# recv_board.net
KiCad netlist of a schematic drawn in Altium Designer
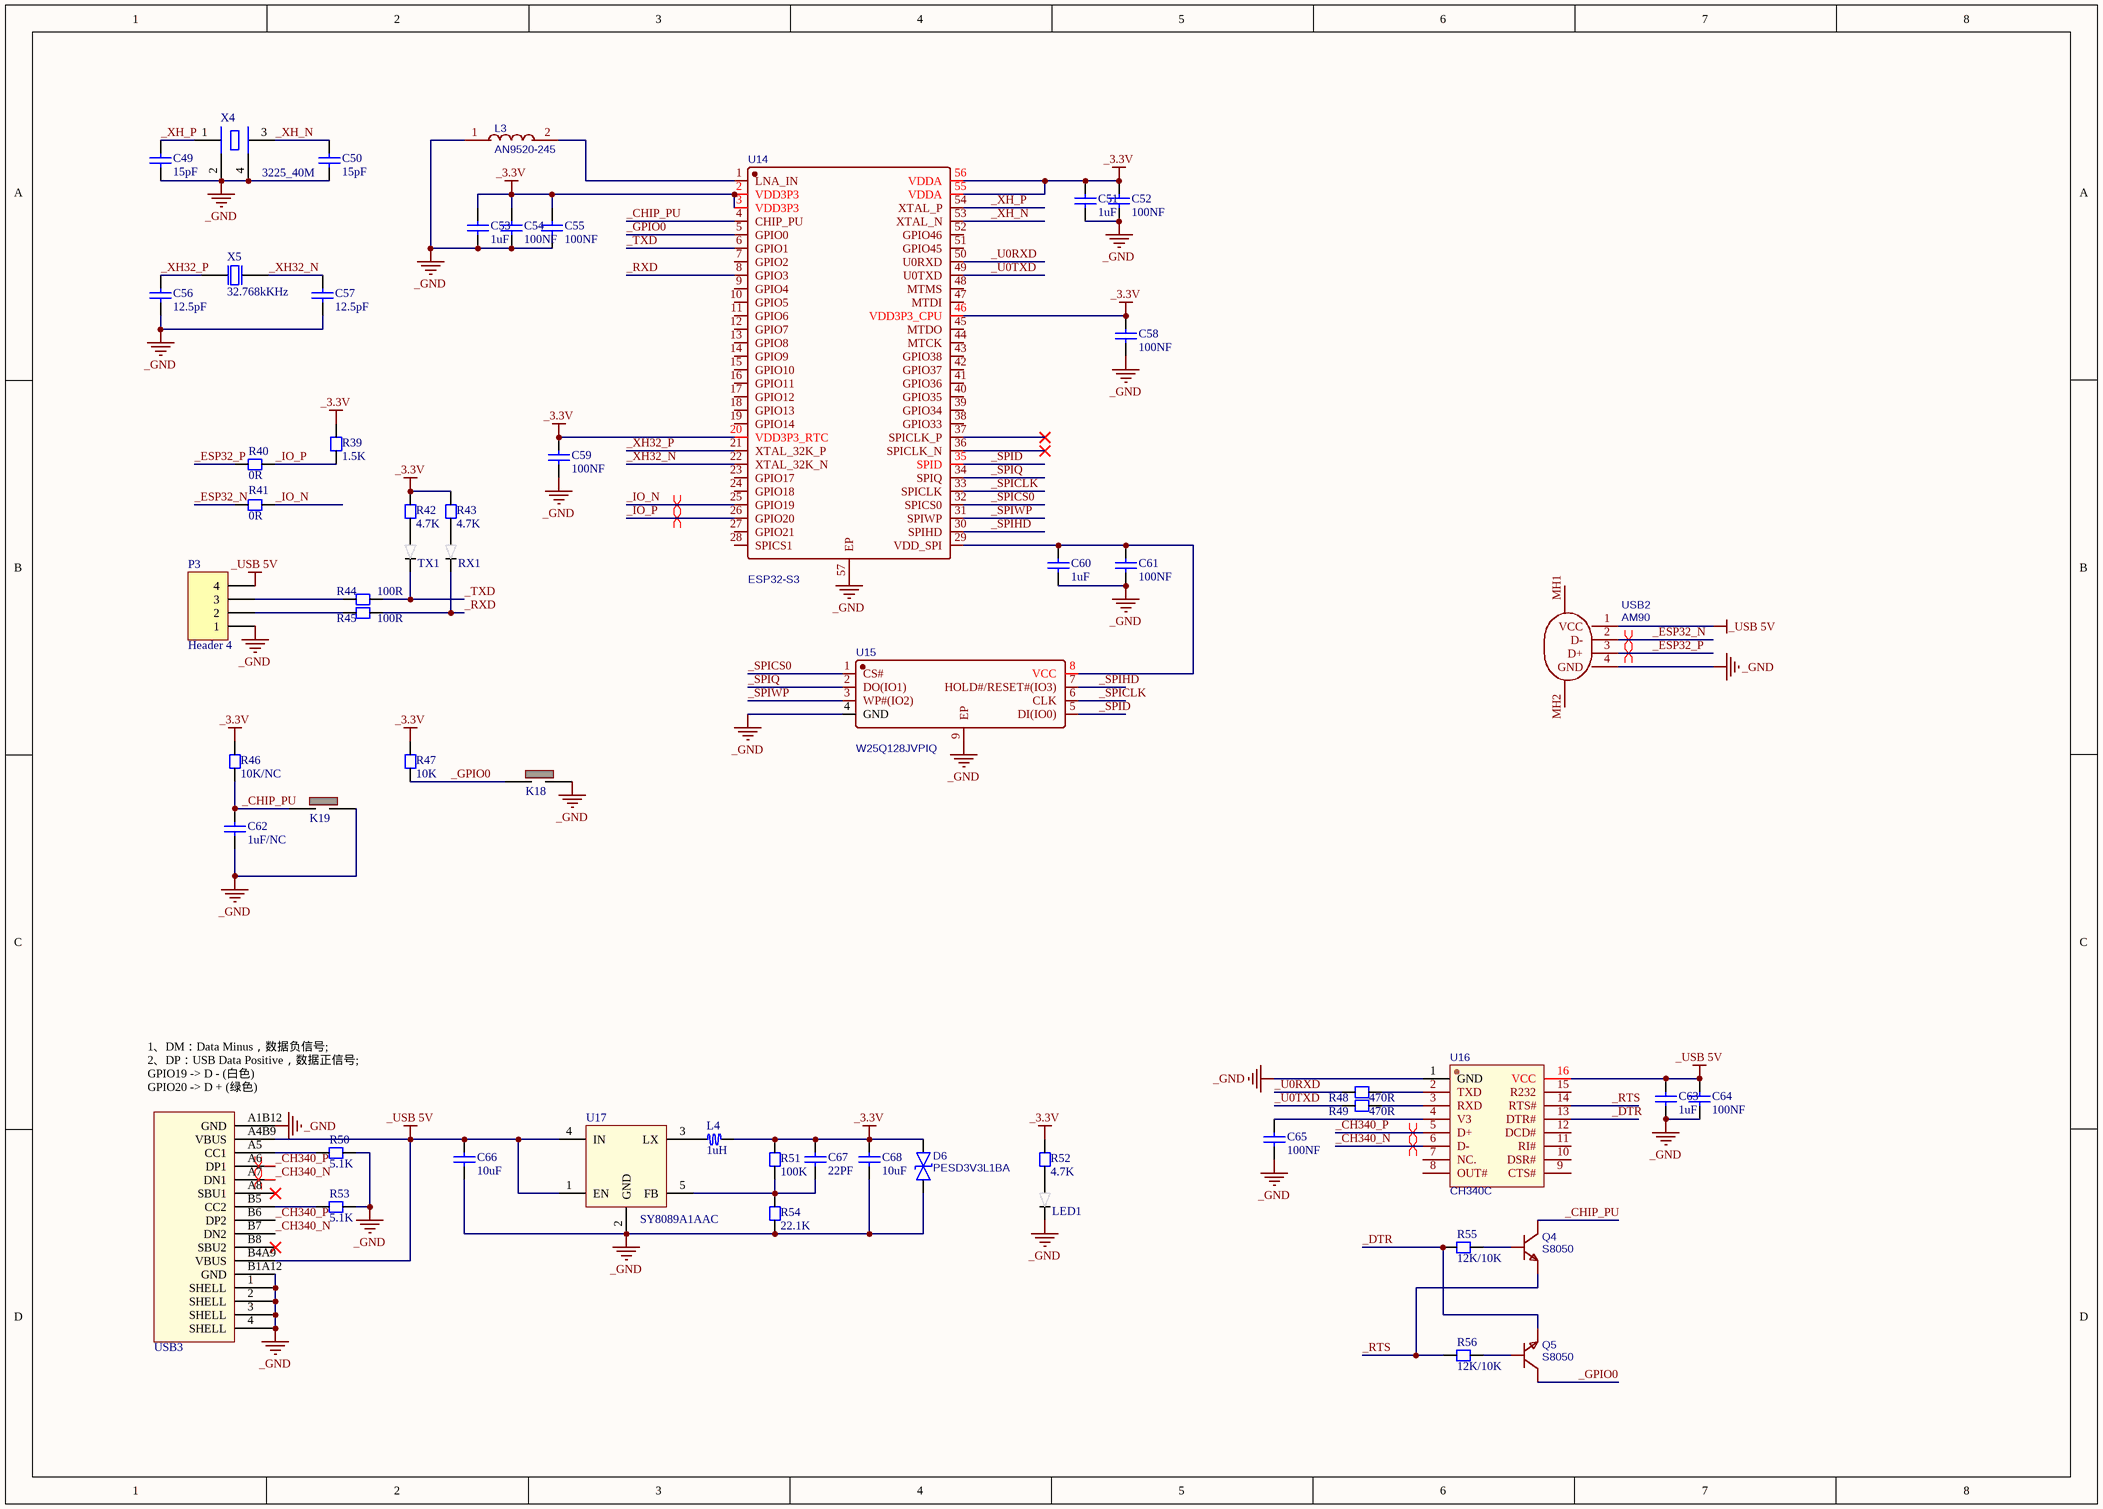
[diagram p0: recv_board.SchDoc]

(export (version "E")
  (design (tool "Eeschema 10.0.6"))
  (components
    (comp (ref "C49")
      (value "15pF")
      (footprint "CC1608-0603")
      (description "0603封装的电容")
      (fields (field (name "PUBLISHER") "Altium Limited"))
      (libsource (lib "base") (part "Cap Chip 0603"))
    )
    (comp (ref "C50")
      (value "15pF")
      (footprint "CC1608-0603")
      (description "0603封装的电容")
      (fields (field (name "PUBLISHER") "Altium Limited"))
      (libsource (lib "base") (part "Cap Chip 0603"))
    )
    (comp (ref "C51")
      (value "1uF")
      (footprint "CC1608-0603")
      (description "0603封装的电容")
      (fields (field (name "PUBLISHER") "Altium Limited"))
      (libsource (lib "base") (part "Cap Chip 0603"))
    )
    (comp (ref "C52")
      (value "100NF")
      (footprint "CC1608-0603")
      (description "0603封装的电容")
      (fields (field (name "PUBLISHER") "Altium Limited"))
      (libsource (lib "base") (part "Cap Chip 0603"))
    )
    (comp (ref "C53")
      (value "1uF")
      (footprint "CC1608-0603")
      (description "0603封装的电容")
      (fields (field (name "PUBLISHER") "Altium Limited"))
      (libsource (lib "base") (part "Cap Chip 0603"))
    )
    (comp (ref "C54")
      (value "100NF")
      (footprint "CC1608-0603")
      (description "0603封装的电容")
      (fields (field (name "PUBLISHER") "Altium Limited"))
      (libsource (lib "base") (part "Cap Chip 0603"))
    )
    (comp (ref "C55")
      (value "100NF")
      (footprint "CC1608-0603")
      (description "0603封装的电容")
      (fields (field (name "PUBLISHER") "Altium Limited"))
      (libsource (lib "base") (part "Cap Chip 0603"))
    )
    (comp (ref "C56")
      (value "12.5pF")
      (footprint "CC1608-0603")
      (description "0603封装的电容")
      (fields (field (name "PUBLISHER") "Altium Limited"))
      (libsource (lib "base") (part "Cap Chip 0603"))
    )
    (comp (ref "C57")
      (value "12.5pF")
      (footprint "CC1608-0603")
      (description "0603封装的电容")
      (fields (field (name "PUBLISHER") "Altium Limited"))
      (libsource (lib "base") (part "Cap Chip 0603"))
    )
    (comp (ref "C58")
      (value "100NF")
      (footprint "CC1608-0603")
      (description "0603封装的电容")
      (fields (field (name "PUBLISHER") "Altium Limited"))
      (libsource (lib "base") (part "Cap Chip 0603"))
    )
    (comp (ref "C59")
      (value "100NF")
      (footprint "CC1608-0603")
      (description "0603封装的电容")
      (fields (field (name "PUBLISHER") "Altium Limited"))
      (libsource (lib "base") (part "Cap Chip 0603"))
    )
    (comp (ref "C60")
      (value "1uF")
      (footprint "CC1608-0603")
      (description "0603封装的电容")
      (fields (field (name "PUBLISHER") "Altium Limited"))
      (libsource (lib "base") (part "Cap Chip 0603"))
    )
    (comp (ref "C61")
      (value "100NF")
      (footprint "CC1608-0603")
      (description "0603封装的电容")
      (fields (field (name "PUBLISHER") "Altium Limited"))
      (libsource (lib "base") (part "Cap Chip 0603"))
    )
    (comp (ref "C62")
      (value "1uF/NC")
      (footprint "CC1608-0603")
      (description "0603封装的电容")
      (fields (field (name "PUBLISHER") "Altium Limited"))
      (libsource (lib "base") (part "Cap Chip 0603"))
    )
    (comp (ref "C63")
      (value "1uF")
      (footprint "CC1608-0603")
      (description "0603封装的电容")
      (fields (field (name "PUBLISHER") "Altium Limited"))
      (libsource (lib "base") (part "Cap Chip 0603"))
    )
    (comp (ref "C64")
      (value "100NF")
      (footprint "CC1608-0603")
      (description "0603封装的电容")
      (fields (field (name "PUBLISHER") "Altium Limited"))
      (libsource (lib "base") (part "Cap Chip 0603"))
    )
    (comp (ref "C65")
      (value "100NF")
      (footprint "CC1608-0603")
      (description "0603封装的电容")
      (fields (field (name "PUBLISHER") "Altium Limited"))
      (libsource (lib "base") (part "Cap Chip 0603"))
    )
    (comp (ref "C66")
      (value "10uF")
      (footprint "CC1608-0603")
      (description "0603封装的电容")
      (fields (field (name "PUBLISHER") "Altium Limited"))
      (libsource (lib "base") (part "Cap Chip 0603"))
    )
    (comp (ref "C67")
      (value "22PF")
      (footprint "CC1608-0603")
      (description "0603封装的电容")
      (fields (field (name "PUBLISHER") "Altium Limited"))
      (libsource (lib "base") (part "Cap Chip 0603"))
    )
    (comp (ref "C68")
      (value "10uF")
      (footprint "CC1608-0603")
      (description "0603封装的电容")
      (fields (field (name "PUBLISHER") "Altium Limited"))
      (libsource (lib "base") (part "Cap Chip 0603"))
    )
    (comp (ref "D6")
      (value "PESD3V3L1BA")
      (footprint "SOD-323")
      (description "SOD-323 3.3V 双向ESD防静电二极管保护芯片")
      (fields (field (name "MANUFACTURER") "MDD") (field (name "MANUFACTURER PART") "SMAJ6.5CA"))
      (libsource (lib "transistor") (part "PESD3V3L1BA"))
    )
    (comp (ref "K18")
      (value "KEY 3*4")
      (footprint "KEY 3*4")
      (description "轻触开关按键")
      (libsource (lib "base") (part "KEY 3*4"))
    )
    (comp (ref "K19")
      (value "KEY 3*4")
      (footprint "KEY 3*4")
      (description "轻触开关按键")
      (libsource (lib "base") (part "KEY 3*4"))
    )
    (comp (ref "L3")
      (value "AN9520-245")
      (footprint "ANT-SMD_L9.5-W2.1")
      (fields (field (name "MANUFACTURER") "rainsun(霖昱微)"))
      (libsource (lib "antenna") (part "AN9520-245"))
    )
    (comp (ref "L4")
      (value "1uH")
      (footprint "Inductor-4018")
      (description "贴片电感 1206封装")
      (libsource (lib "base") (part "Inductor-4018"))
    )
    (comp (ref "LED1") (value "LED 0603") (footprint "LED 0603") (libsource (lib "base") (part "LED 0603")))
    (comp (ref "P3")
      (value "Header 4")
      (footprint "HDR1X4")
      (description "Header, 4-Pin")
      (fields (field (name "PUBLISHER") "Altium Limited"))
      (libsource (lib "Connectors") (part "Header 4"))
    )
    (comp (ref "Q4")
      (value "S8050")
      (footprint "SOT-23")
      (fields (field (name "MANUFACTURER") "SALLTECH(萨瑞)") (field (name "CONTRIBUTOR") "lcsc"))
      (libsource (lib "transistor") (part "S8050"))
    )
    (comp (ref "Q5")
      (value "S8050")
      (footprint "SOT-23")
      (fields (field (name "MANUFACTURER") "SALLTECH(萨瑞)") (field (name "CONTRIBUTOR") "lcsc"))
      (libsource (lib "transistor") (part "S8050"))
    )
    (comp (ref "R39")
      (value "1.5K")
      (footprint "CR1608-0603")
      (description "0603封装电阻")
      (fields (field (name "PUBLISHER") "Altium Limited"))
      (libsource (lib "") (part "Resistor Chip 0603_1"))
    )
    (comp (ref "R40")
      (value "0R")
      (footprint "CR1608-0603")
      (description "0603封装电阻")
      (fields (field (name "PUBLISHER") "Altium Limited"))
      (libsource (lib "base") (part "Resistor Chip 0603"))
    )
    (comp (ref "R41")
      (value "0R")
      (footprint "CR1608-0603")
      (description "0603封装电阻")
      (fields (field (name "PUBLISHER") "Altium Limited"))
      (libsource (lib "base") (part "Resistor Chip 0603"))
    )
    (comp (ref "R42")
      (value "4.7K")
      (footprint "CR1608-0603")
      (description "0603封装电阻")
      (fields (field (name "PUBLISHER") "Altium Limited"))
      (libsource (lib "") (part "Resistor Chip 0603_1"))
    )
    (comp (ref "R43")
      (value "4.7K")
      (footprint "CR1608-0603")
      (description "0603封装电阻")
      (fields (field (name "PUBLISHER") "Altium Limited"))
      (libsource (lib "") (part "Resistor Chip 0603_1"))
    )
    (comp (ref "R44")
      (value "100R")
      (footprint "CR1608-0603")
      (description "0603封装电阻")
      (fields (field (name "PUBLISHER") "Altium Limited"))
      (libsource (lib "base") (part "Resistor Chip 0603"))
    )
    (comp (ref "R45")
      (value "100R")
      (footprint "CR1608-0603")
      (description "0603封装电阻")
      (fields (field (name "PUBLISHER") "Altium Limited"))
      (libsource (lib "base") (part "Resistor Chip 0603"))
    )
    (comp (ref "R46")
      (value "10K/NC")
      (footprint "CR1608-0603")
      (description "0603封装电阻")
      (fields (field (name "PUBLISHER") "Altium Limited"))
      (libsource (lib "") (part "Resistor Chip 0603_3"))
    )
    (comp (ref "R47")
      (value "10K")
      (footprint "CR1608-0603")
      (description "0603封装电阻")
      (fields (field (name "PUBLISHER") "Altium Limited"))
      (libsource (lib "") (part "Resistor Chip 0603_3"))
    )
    (comp (ref "R48")
      (value "470R")
      (footprint "CR1608-0603")
      (description "0603封装电阻")
      (fields (field (name "PUBLISHER") "Altium Limited"))
      (libsource (lib "base") (part "Resistor Chip 0603"))
    )
    (comp (ref "R49")
      (value "470R")
      (footprint "CR1608-0603")
      (description "0603封装电阻")
      (fields (field (name "PUBLISHER") "Altium Limited"))
      (libsource (lib "base") (part "Resistor Chip 0603"))
    )
    (comp (ref "R50")
      (value "5.1K")
      (footprint "CR1608-0603")
      (description "0603封装电阻")
      (fields (field (name "PUBLISHER") "Altium Limited"))
      (libsource (lib "base") (part "Resistor Chip 0603"))
    )
    (comp (ref "R51")
      (value "100K")
      (footprint "CR1608-0603")
      (description "0603封装电阻")
      (fields (field (name "PUBLISHER") "Altium Limited"))
      (libsource (lib "") (part "Resistor Chip 0603_1"))
    )
    (comp (ref "R52")
      (value "4.7K")
      (footprint "CR1608-0603")
      (description "0603封装电阻")
      (fields (field (name "PUBLISHER") "Altium Limited"))
      (libsource (lib "") (part "Resistor Chip 0603_1"))
    )
    (comp (ref "R53")
      (value "5.1K")
      (footprint "CR1608-0603")
      (description "0603封装电阻")
      (fields (field (name "PUBLISHER") "Altium Limited"))
      (libsource (lib "base") (part "Resistor Chip 0603"))
    )
    (comp (ref "R54")
      (value "22.1K")
      (footprint "CR1608-0603")
      (description "0603封装电阻")
      (fields (field (name "PUBLISHER") "Altium Limited"))
      (libsource (lib "") (part "Resistor Chip 0603_1"))
    )
    (comp (ref "R55")
      (value "12K/10K")
      (footprint "CR1608-0603")
      (description "0603封装电阻")
      (fields (field (name "PUBLISHER") "Altium Limited"))
      (libsource (lib "") (part "Resistor Chip 0603_2"))
    )
    (comp (ref "R56")
      (value "12K/10K")
      (footprint "CR1608-0603")
      (description "0603封装电阻")
      (fields (field (name "PUBLISHER") "Altium Limited"))
      (libsource (lib "") (part "Resistor Chip 0603_3"))
    )
    (comp (ref "RX1") (value "LED 0603") (footprint "LED 0603") (libsource (lib "base") (part "LED 0603")))
    (comp (ref "TX1") (value "LED 0603") (footprint "LED 0603") (libsource (lib "base") (part "LED 0603")))
    (comp (ref "U14")
      (value "ESP32-S3")
      (footprint "QFN-56")
      (fields (field (name "MANUFACTURER") "ESPRESSIF(乐鑫)") (field (name "CONTRIBUTOR") "LCSC"))
      (libsource (lib "singlechip") (part "ESP32-S3"))
    )
    (comp (ref "U15")
      (value "W25Q128JVPIQ")
      (footprint "WSON-8")
      (fields (field (name "MANUFACTURER") "WINBOND(华邦)") (field (name "CONTRIBUTOR") "LCSC"))
      (libsource (lib "PB-Chip") (part "W25Q128JVPIQ"))
    )
    (comp (ref "U16")
      (value "CH340C")
      (footprint "SOP-16")
      (fields (field (name "MANUFACTURER") "WCH(南京沁恒)"))
      (libsource (lib "PB-Chip") (part "CH340C"))
    )
    (comp (ref "U17")
      (value "SY8089A1AAC")
      (footprint "SOT23-5")
      (libsource (lib "power-chip") (part "SY8089A1AAC"))
    )
    (comp (ref "USB2")
      (value "AM90")
      (footprint "USB-AM")
      (fields (field (name "MANUFACTURER") "SHOU HAN(首韩)") (field (name "CONTRIBUTOR") "LCSC"))
      (libsource (lib "Connectors") (part "USB-AM90"))
    )
    (comp (ref "USB3")
      (value "Tpye-c 16P")
      (footprint "TYPE-C 16P")
      (description "16P 封装的TYPE -c接口 4固定插脚 双向")
      (libsource (lib "Connectors") (part "Tpye-c 16P"))
    )
    (comp (ref "X4")
      (value "3225_40M")
      (footprint "XTAL-3225")
      (description "3225封装的晶振")
      (libsource (lib "base") (part "XTAL 3225"))
    )
    (comp (ref "X5")
      (value "32.768kKHz")
      (footprint "XTAL-3215")
      (description "3215封装的时钟晶振")
      (libsource (lib "base") (part "XTAL 3215 32.768kKHz"))
    )
  )
  (nets
    (net (code "1") (name "/_CH340_N") (class "Default")
      (node (ref "U16") (pin "6") (pinfunction "D-_6") (pintype "passive"))
      (node (ref "USB3") (pin "A7") (pinfunction "DN1_A7") (pintype "power_in"))
      (node (ref "USB3") (pin "B7") (pinfunction "DN2_B7") (pintype "power_in"))
    )
    (net (code "2") (name "/_CH340_P") (class "Default")
      (node (ref "U16") (pin "5") (pinfunction "D+_5") (pintype "passive"))
      (node (ref "USB3") (pin "A6") (pinfunction "DP1_A6") (pintype "power_in"))
      (node (ref "USB3") (pin "B6") (pinfunction "DP2_B6") (pintype "power_in"))
    )
    (net (code "3") (name "/_CHIP_PU") (class "Default")
      (node (ref "C62") (pin "2") (pinfunction "2_2") (pintype "passive"))
      (node (ref "K19") (pin "1") (pinfunction "1_1") (pintype "passive"))
      (node (ref "Q4") (pin "3") (pinfunction "C_3") (pintype "passive"))
      (node (ref "R46") (pin "1") (pinfunction "1_1") (pintype "passive"))
      (node (ref "U14") (pin "4") (pinfunction "CHIP_PU_4") (pintype "passive"))
    )
    (net (code "4") (name "/_DTR") (class "Default")
      (node (ref "Q5") (pin "2") (pinfunction "E_2") (pintype "passive"))
      (node (ref "R55") (pin "1") (pinfunction "1_1") (pintype "passive"))
      (node (ref "U16") (pin "13") (pinfunction "DTR#_13") (pintype "passive"))
    )
    (net (code "5") (name "/_ESP32_N") (class "Default")
      (node (ref "R41") (pin "2") (pinfunction "2_2") (pintype "passive"))
      (node (ref "USB2") (pin "2") (pinfunction "D-_2") (pintype "passive"))
    )
    (net (code "6") (name "/_ESP32_P") (class "Default")
      (node (ref "R40") (pin "2") (pinfunction "2_2") (pintype "passive"))
      (node (ref "USB2") (pin "3") (pinfunction "D+_3") (pintype "passive"))
    )
    (net (code "7") (name "/_GPIO0") (class "Default")
      (node (ref "K18") (pin "1") (pinfunction "1_1") (pintype "passive"))
      (node (ref "Q5") (pin "3") (pinfunction "C_3") (pintype "passive"))
      (node (ref "R47") (pin "1") (pinfunction "1_1") (pintype "passive"))
      (node (ref "U14") (pin "5") (pinfunction "GPIO0_5") (pintype "passive"))
    )
    (net (code "8") (name "/_IO_N") (class "Default")
      (node (ref "R41") (pin "1") (pinfunction "1_1") (pintype "passive"))
      (node (ref "U14") (pin "25") (pinfunction "GPIO19_25") (pintype "passive"))
    )
    (net (code "9") (name "/_IO_P") (class "Default")
      (node (ref "R39") (pin "2") (pinfunction "2_2") (pintype "passive"))
      (node (ref "R40") (pin "1") (pinfunction "1_1") (pintype "passive"))
      (node (ref "U14") (pin "26") (pinfunction "GPIO20_26") (pintype "passive"))
    )
    (net (code "10") (name "/_RTS") (class "Default")
      (node (ref "Q4") (pin "2") (pinfunction "E_2") (pintype "passive"))
      (node (ref "R56") (pin "1") (pinfunction "1_1") (pintype "passive"))
      (node (ref "U16") (pin "14") (pinfunction "RTS#_14") (pintype "passive"))
    )
    (net (code "11") (name "/_RXD") (class "Default")
      (node (ref "R45") (pin "1") (pinfunction "1_1") (pintype "passive"))
      (node (ref "RX1") (pin "2") (pinfunction "2_2") (pintype "passive"))
      (node (ref "U14") (pin "8") (pinfunction "GPIO3_8") (pintype "passive"))
    )
    (net (code "12") (name "/_SPICLK") (class "Default")
      (node (ref "U14") (pin "33") (pinfunction "SPICLK_33") (pintype "passive"))
      (node (ref "U15") (pin "6") (pinfunction "CLK_6") (pintype "passive"))
    )
    (net (code "13") (name "/_SPICS0") (class "Default")
      (node (ref "U14") (pin "32") (pinfunction "SPICS0_32") (pintype "passive"))
      (node (ref "U15") (pin "1") (pinfunction "CS#_1") (pintype "passive"))
    )
    (net (code "14") (name "/_SPID") (class "Default")
      (node (ref "U14") (pin "35") (pinfunction "SPID_35") (pintype "passive"))
      (node (ref "U15") (pin "5") (pinfunction "DI(IO0)_5") (pintype "passive"))
    )
    (net (code "15") (name "/_SPIHD") (class "Default")
      (node (ref "U14") (pin "30") (pinfunction "SPIHD_30") (pintype "passive"))
      (node (ref "U15") (pin "7") (pinfunction "HOLD#/RESET#(IO3)_7") (pintype "passive"))
    )
    (net (code "16") (name "/_SPIQ") (class "Default")
      (node (ref "U14") (pin "34") (pinfunction "SPIQ_34") (pintype "passive"))
      (node (ref "U15") (pin "2") (pinfunction "DO(IO1)_2") (pintype "passive"))
    )
    (net (code "17") (name "/_SPIWP") (class "Default")
      (node (ref "U14") (pin "31") (pinfunction "SPIWP_31") (pintype "passive"))
      (node (ref "U15") (pin "3") (pinfunction "WP#(IO2)_3") (pintype "passive"))
    )
    (net (code "18") (name "/_TXD") (class "Default")
      (node (ref "R44") (pin "1") (pinfunction "1_1") (pintype "passive"))
      (node (ref "TX1") (pin "2") (pinfunction "2_2") (pintype "passive"))
      (node (ref "U14") (pin "6") (pinfunction "GPIO1_6") (pintype "passive"))
    )
    (net (code "19") (name "/_U0RXD") (class "Default")
      (node (ref "R48") (pin "2") (pinfunction "2_2") (pintype "passive"))
      (node (ref "U14") (pin "50") (pinfunction "U0RXD_50") (pintype "passive"))
    )
    (net (code "20") (name "/_U0TXD") (class "Default")
      (node (ref "R49") (pin "2") (pinfunction "2_2") (pintype "passive"))
      (node (ref "U14") (pin "49") (pinfunction "U0TXD_49") (pintype "passive"))
    )
    (net (code "21") (name "/_XH32_N") (class "Default")
      (node (ref "C57") (pin "2") (pinfunction "2_2") (pintype "passive"))
      (node (ref "U14") (pin "22") (pinfunction "XTAL_32K_N_22") (pintype "passive"))
      (node (ref "X5") (pin "2") (pinfunction "OSC2_2") (pintype "passive"))
    )
    (net (code "22") (name "/_XH32_P") (class "Default")
      (node (ref "C56") (pin "2") (pinfunction "2_2") (pintype "passive"))
      (node (ref "U14") (pin "21") (pinfunction "XTAL_32K_P_21") (pintype "passive"))
      (node (ref "X5") (pin "1") (pinfunction "OSC1_1") (pintype "passive"))
    )
    (net (code "23") (name "/_XH_N") (class "Default")
      (node (ref "C50") (pin "2") (pinfunction "2_2") (pintype "passive"))
      (node (ref "U14") (pin "53") (pinfunction "XTAL_N_53") (pintype "passive"))
      (node (ref "X4") (pin "3") (pinfunction "OSC2_3") (pintype "passive"))
    )
    (net (code "24") (name "/_XH_P") (class "Default")
      (node (ref "C49") (pin "2") (pinfunction "2_2") (pintype "passive"))
      (node (ref "U14") (pin "54") (pinfunction "XTAL_P_54") (pintype "passive"))
      (node (ref "X4") (pin "1") (pinfunction "OSC1_1") (pintype "passive"))
    )
    (net (code "25") (name "Net-(LED1-Pad1)") (class "Default")
      (node (ref "LED1") (pin "1") (pinfunction "1_1") (pintype "passive"))
      (node (ref "R52") (pin "2") (pinfunction "2_2") (pintype "passive"))
    )
    (net (code "26") (name "Net-(P3-Pad2)") (class "Default")
      (node (ref "P3") (pin "2") (pinfunction "2_2") (pintype "passive"))
      (node (ref "R45") (pin "2") (pinfunction "2_2") (pintype "passive"))
    )
    (net (code "27") (name "Net-(P3-Pad3)") (class "Default")
      (node (ref "P3") (pin "3") (pinfunction "3_3") (pintype "passive"))
      (node (ref "R44") (pin "2") (pinfunction "2_2") (pintype "passive"))
    )
    (net (code "28") (name "Net-(Q4-B)") (class "Default")
      (node (ref "Q4") (pin "1") (pinfunction "B_1") (pintype "passive"))
      (node (ref "R55") (pin "2") (pinfunction "2_2") (pintype "passive"))
    )
    (net (code "29") (name "Net-(Q5-B)") (class "Default")
      (node (ref "Q5") (pin "1") (pinfunction "B_1") (pintype "passive"))
      (node (ref "R56") (pin "2") (pinfunction "2_2") (pintype "passive"))
    )
    (net (code "30") (name "Net-(R42-Pad2)") (class "Default")
      (node (ref "R42") (pin "2") (pinfunction "2_2") (pintype "passive"))
      (node (ref "TX1") (pin "1") (pinfunction "1_1") (pintype "passive"))
    )
    (net (code "31") (name "Net-(R43-Pad2)") (class "Default")
      (node (ref "R43") (pin "2") (pinfunction "2_2") (pintype "passive"))
      (node (ref "RX1") (pin "1") (pinfunction "1_1") (pintype "passive"))
    )
    (net (code "32") (name "Net-(U14-LNA_IN)") (class "Default")
      (node (ref "L3") (pin "2") (pinfunction "2_2") (pintype "passive"))
      (node (ref "U14") (pin "1") (pinfunction "LNA_IN_1") (pintype "passive"))
    )
    (net (code "33") (name "Net-(U14-VDD_SPI)") (class "Default")
      (node (ref "C60") (pin "2") (pinfunction "2_2") (pintype "passive"))
      (node (ref "C61") (pin "2") (pinfunction "2_2") (pintype "passive"))
      (node (ref "U14") (pin "29") (pinfunction "VDD_SPI_29") (pintype "passive"))
      (node (ref "U15") (pin "8") (pinfunction "VCC_8") (pintype "passive"))
    )
    (net (code "34") (name "Net-(U16-RXD)") (class "Default")
      (node (ref "R49") (pin "1") (pinfunction "1_1") (pintype "passive"))
      (node (ref "U16") (pin "3") (pinfunction "RXD_3") (pintype "passive"))
    )
    (net (code "35") (name "Net-(U16-TXD)") (class "Default")
      (node (ref "R48") (pin "1") (pinfunction "1_1") (pintype "passive"))
      (node (ref "U16") (pin "2") (pinfunction "TXD_2") (pintype "passive"))
    )
    (net (code "36") (name "Net-(U16-V3)") (class "Default")
      (node (ref "C65") (pin "2") (pinfunction "2_2") (pintype "passive"))
      (node (ref "U16") (pin "4") (pinfunction "V3_4") (pintype "passive"))
    )
    (net (code "37") (name "Net-(U17-FB)") (class "Default")
      (node (ref "C67") (pin "1") (pinfunction "1_1") (pintype "passive"))
      (node (ref "R51") (pin "2") (pinfunction "2_2") (pintype "passive"))
      (node (ref "R54") (pin "1") (pinfunction "1_1") (pintype "passive"))
      (node (ref "U17") (pin "5") (pinfunction "FB_5") (pintype "passive"))
    )
    (net (code "38") (name "Net-(U17-LX)") (class "Default")
      (node (ref "L4") (pin "1") (pinfunction "1_1") (pintype "passive"))
      (node (ref "U17") (pin "3") (pinfunction "LX_3") (pintype "passive"))
    )
    (net (code "39") (name "Net-(USB3-CC1)") (class "Default")
      (node (ref "R50") (pin "2") (pinfunction "2_2") (pintype "passive"))
      (node (ref "USB3") (pin "A5") (pinfunction "CC1_A5") (pintype "power_in"))
    )
    (net (code "40") (name "Net-(USB3-CC2)") (class "Default")
      (node (ref "R53") (pin "2") (pinfunction "2_2") (pintype "passive"))
      (node (ref "USB3") (pin "B5") (pinfunction "CC2_B5") (pintype "power_in"))
    )
    (net (code "41") (name "_3.3V") (class "Default")
      (node (ref "C51") (pin "2") (pinfunction "2_2") (pintype "passive"))
      (node (ref "C52") (pin "2") (pinfunction "2_2") (pintype "passive"))
      (node (ref "C53") (pin "2") (pinfunction "2_2") (pintype "passive"))
      (node (ref "C54") (pin "2") (pinfunction "2_2") (pintype "passive"))
      (node (ref "C55") (pin "2") (pinfunction "2_2") (pintype "passive"))
      (node (ref "C58") (pin "2") (pinfunction "2_2") (pintype "passive"))
      (node (ref "C59") (pin "2") (pinfunction "2_2") (pintype "passive"))
      (node (ref "C67") (pin "2") (pinfunction "2_2") (pintype "passive"))
      (node (ref "C68") (pin "2") (pinfunction "2_2") (pintype "passive"))
      (node (ref "D6") (pin "1") (pinfunction "1_1") (pintype "passive"))
      (node (ref "L4") (pin "2") (pinfunction "2_2") (pintype "passive"))
      (node (ref "R39") (pin "1") (pinfunction "1_1") (pintype "passive"))
      (node (ref "R42") (pin "1") (pinfunction "1_1") (pintype "passive"))
      (node (ref "R43") (pin "1") (pinfunction "1_1") (pintype "passive"))
      (node (ref "R46") (pin "2") (pinfunction "2_2") (pintype "passive"))
      (node (ref "R47") (pin "2") (pinfunction "2_2") (pintype "passive"))
      (node (ref "R51") (pin "1") (pinfunction "1_1") (pintype "passive"))
      (node (ref "R52") (pin "1") (pinfunction "1_1") (pintype "passive"))
      (node (ref "U14") (pin "2") (pinfunction "VDD3P3_2") (pintype "passive"))
      (node (ref "U14") (pin "20") (pinfunction "VDD3P3_RTC_20") (pintype "passive"))
      (node (ref "U14") (pin "3") (pinfunction "VDD3P3_3") (pintype "passive"))
      (node (ref "U14") (pin "46") (pinfunction "VDD3P3_CPU_46") (pintype "passive"))
      (node (ref "U14") (pin "55") (pinfunction "VDDA_55") (pintype "passive"))
      (node (ref "U14") (pin "56") (pinfunction "VDDA_56") (pintype "passive"))
    )
    (net (code "42") (name "_GND") (class "Default")
      (node (ref "C49") (pin "1") (pinfunction "1_1") (pintype "passive"))
      (node (ref "C50") (pin "1") (pinfunction "1_1") (pintype "passive"))
      (node (ref "C51") (pin "1") (pinfunction "1_1") (pintype "passive"))
      (node (ref "C52") (pin "1") (pinfunction "1_1") (pintype "passive"))
      (node (ref "C53") (pin "1") (pinfunction "1_1") (pintype "passive"))
      (node (ref "C54") (pin "1") (pinfunction "1_1") (pintype "passive"))
      (node (ref "C55") (pin "1") (pinfunction "1_1") (pintype "passive"))
      (node (ref "C56") (pin "1") (pinfunction "1_1") (pintype "passive"))
      (node (ref "C57") (pin "1") (pinfunction "1_1") (pintype "passive"))
      (node (ref "C58") (pin "1") (pinfunction "1_1") (pintype "passive"))
      (node (ref "C59") (pin "1") (pinfunction "1_1") (pintype "passive"))
      (node (ref "C60") (pin "1") (pinfunction "1_1") (pintype "passive"))
      (node (ref "C61") (pin "1") (pinfunction "1_1") (pintype "passive"))
      (node (ref "C62") (pin "1") (pinfunction "1_1") (pintype "passive"))
      (node (ref "C63") (pin "1") (pinfunction "1_1") (pintype "passive"))
      (node (ref "C64") (pin "1") (pinfunction "1_1") (pintype "passive"))
      (node (ref "C65") (pin "1") (pinfunction "1_1") (pintype "passive"))
      (node (ref "C66") (pin "1") (pinfunction "1_1") (pintype "passive"))
      (node (ref "C68") (pin "1") (pinfunction "1_1") (pintype "passive"))
      (node (ref "D6") (pin "2") (pinfunction "2_2") (pintype "passive"))
      (node (ref "K18") (pin "2") (pinfunction "2_2") (pintype "passive"))
      (node (ref "K19") (pin "2") (pinfunction "2_2") (pintype "passive"))
      (node (ref "L3") (pin "1") (pinfunction "1_1") (pintype "passive"))
      (node (ref "LED1") (pin "2") (pinfunction "2_2") (pintype "passive"))
      (node (ref "P3") (pin "1") (pinfunction "1_1") (pintype "passive"))
      (node (ref "R50") (pin "1") (pinfunction "1_1") (pintype "passive"))
      (node (ref "R53") (pin "1") (pinfunction "1_1") (pintype "passive"))
      (node (ref "R54") (pin "2") (pinfunction "2_2") (pintype "passive"))
      (node (ref "U14") (pin "57") (pinfunction "EP_57") (pintype "passive"))
      (node (ref "U15") (pin "4") (pinfunction "GND_4") (pintype "passive"))
      (node (ref "U15") (pin "9") (pinfunction "EP_9") (pintype "passive"))
      (node (ref "U16") (pin "1") (pinfunction "GND_1") (pintype "passive"))
      (node (ref "U17") (pin "2") (pinfunction "GND_2") (pintype "passive"))
      (node (ref "USB2") (pin "4") (pinfunction "GND_4") (pintype "passive"))
      (node (ref "USB3") (pin "1") (pinfunction "SHELL_1") (pintype "power_in"))
      (node (ref "USB3") (pin "2") (pinfunction "SHELL_2") (pintype "power_in"))
      (node (ref "USB3") (pin "3") (pinfunction "SHELL_3") (pintype "power_in"))
      (node (ref "USB3") (pin "4") (pinfunction "SHELL_4") (pintype "power_in"))
      (node (ref "USB3") (pin "A1B12") (pinfunction "GND_A1B12") (pintype "power_in"))
      (node (ref "USB3") (pin "B1A12") (pinfunction "GND_B1A12") (pintype "power_in"))
      (node (ref "X4") (pin "2") (pinfunction "GND_2") (pintype "passive"))
      (node (ref "X4") (pin "4") (pinfunction "GND_4") (pintype "passive"))
    )
    (net (code "43") (name "_USB 5V") (class "Default")
      (node (ref "C63") (pin "2") (pinfunction "2_2") (pintype "passive"))
      (node (ref "C64") (pin "2") (pinfunction "2_2") (pintype "passive"))
      (node (ref "C66") (pin "2") (pinfunction "2_2") (pintype "passive"))
      (node (ref "P3") (pin "4") (pinfunction "4_4") (pintype "passive"))
      (node (ref "U16") (pin "16") (pinfunction "VCC_16") (pintype "passive"))
      (node (ref "U17") (pin "1") (pinfunction "EN_1") (pintype "passive"))
      (node (ref "U17") (pin "4") (pinfunction "IN_4") (pintype "passive"))
      (node (ref "USB2") (pin "1") (pinfunction "VCC_1") (pintype "passive"))
      (node (ref "USB3") (pin "A4B9") (pinfunction "VBUS_A4B9") (pintype "power_in"))
      (node (ref "USB3") (pin "B4A9") (pinfunction "VBUS_B4A9") (pintype "power_in"))
    )
    (net (code "44") (name "unconnected-(U14-GPIO2-Pad7)") (class "Default")
      (node (ref "U14") (pin "7") (pinfunction "GPIO2_7") (pintype "passive"))
    )
    (net (code "45") (name "unconnected-(U14-GPIO4-Pad9)") (class "Default")
      (node (ref "U14") (pin "9") (pinfunction "GPIO4_9") (pintype "passive"))
    )
    (net (code "46") (name "unconnected-(U14-GPIO5-Pad10)") (class "Default")
      (node (ref "U14") (pin "10") (pinfunction "GPIO5_10") (pintype "passive"))
    )
    (net (code "47") (name "unconnected-(U14-GPIO6-Pad11)") (class "Default")
      (node (ref "U14") (pin "11") (pinfunction "GPIO6_11") (pintype "passive"))
    )
    (net (code "48") (name "unconnected-(U14-GPIO7-Pad12)") (class "Default")
      (node (ref "U14") (pin "12") (pinfunction "GPIO7_12") (pintype "passive"))
    )
    (net (code "49") (name "unconnected-(U14-GPIO8-Pad13)") (class "Default")
      (node (ref "U14") (pin "13") (pinfunction "GPIO8_13") (pintype "passive"))
    )
    (net (code "50") (name "unconnected-(U14-GPIO9-Pad14)") (class "Default")
      (node (ref "U14") (pin "14") (pinfunction "GPIO9_14") (pintype "passive"))
    )
    (net (code "51") (name "unconnected-(U14-GPIO10-Pad15)") (class "Default")
      (node (ref "U14") (pin "15") (pinfunction "GPIO10_15") (pintype "passive"))
    )
    (net (code "52") (name "unconnected-(U14-GPIO11-Pad16)") (class "Default")
      (node (ref "U14") (pin "16") (pinfunction "GPIO11_16") (pintype "passive"))
    )
    (net (code "53") (name "unconnected-(U14-GPIO12-Pad17)") (class "Default")
      (node (ref "U14") (pin "17") (pinfunction "GPIO12_17") (pintype "passive"))
    )
    (net (code "54") (name "unconnected-(U14-GPIO13-Pad18)") (class "Default")
      (node (ref "U14") (pin "18") (pinfunction "GPIO13_18") (pintype "passive"))
    )
    (net (code "55") (name "unconnected-(U14-GPIO14-Pad19)") (class "Default")
      (node (ref "U14") (pin "19") (pinfunction "GPIO14_19") (pintype "passive"))
    )
    (net (code "56") (name "unconnected-(U14-GPIO17-Pad23)") (class "Default")
      (node (ref "U14") (pin "23") (pinfunction "GPIO17_23") (pintype "passive"))
    )
    (net (code "57") (name "unconnected-(U14-GPIO18-Pad24)") (class "Default")
      (node (ref "U14") (pin "24") (pinfunction "GPIO18_24") (pintype "passive"))
    )
    (net (code "58") (name "unconnected-(U14-GPIO21-Pad27)") (class "Default")
      (node (ref "U14") (pin "27") (pinfunction "GPIO21_27") (pintype "passive"))
    )
    (net (code "59") (name "unconnected-(U14-GPIO33-Pad38)") (class "Default")
      (node (ref "U14") (pin "38") (pinfunction "GPIO33_38") (pintype "passive"))
    )
    (net (code "60") (name "unconnected-(U14-GPIO34-Pad39)") (class "Default")
      (node (ref "U14") (pin "39") (pinfunction "GPIO34_39") (pintype "passive"))
    )
    (net (code "61") (name "unconnected-(U14-GPIO35-Pad40)") (class "Default")
      (node (ref "U14") (pin "40") (pinfunction "GPIO35_40") (pintype "passive"))
    )
    (net (code "62") (name "unconnected-(U14-GPIO36-Pad41)") (class "Default")
      (node (ref "U14") (pin "41") (pinfunction "GPIO36_41") (pintype "passive"))
    )
    (net (code "63") (name "unconnected-(U14-GPIO37-Pad42)") (class "Default")
      (node (ref "U14") (pin "42") (pinfunction "GPIO37_42") (pintype "passive"))
    )
    (net (code "64") (name "unconnected-(U14-GPIO38-Pad43)") (class "Default")
      (node (ref "U14") (pin "43") (pinfunction "GPIO38_43") (pintype "passive"))
    )
    (net (code "65") (name "unconnected-(U14-GPIO45-Pad51)") (class "Default")
      (node (ref "U14") (pin "51") (pinfunction "GPIO45_51") (pintype "passive"))
    )
    (net (code "66") (name "unconnected-(U14-GPIO46-Pad52)") (class "Default")
      (node (ref "U14") (pin "52") (pinfunction "GPIO46_52") (pintype "passive"))
    )
    (net (code "67") (name "unconnected-(U14-MTCK-Pad44)") (class "Default")
      (node (ref "U14") (pin "44") (pinfunction "MTCK_44") (pintype "passive"))
    )
    (net (code "68") (name "unconnected-(U14-MTDI-Pad47)") (class "Default")
      (node (ref "U14") (pin "47") (pinfunction "MTDI_47") (pintype "passive"))
    )
    (net (code "69") (name "unconnected-(U14-MTDO-Pad45)") (class "Default")
      (node (ref "U14") (pin "45") (pinfunction "MTDO_45") (pintype "passive"))
    )
    (net (code "70") (name "unconnected-(U14-MTMS-Pad48)") (class "Default")
      (node (ref "U14") (pin "48") (pinfunction "MTMS_48") (pintype "passive"))
    )
    (net (code "71") (name "unconnected-(U14-SPICLK_N-Pad36)") (class "Default")
      (node (ref "U14") (pin "36") (pinfunction "SPICLK_N_36") (pintype "passive+no_connect"))
    )
    (net (code "72") (name "unconnected-(U14-SPICLK_P-Pad37)") (class "Default")
      (node (ref "U14") (pin "37") (pinfunction "SPICLK_P_37") (pintype "passive+no_connect"))
    )
    (net (code "73") (name "unconnected-(U14-SPICS1-Pad28)") (class "Default")
      (node (ref "U14") (pin "28") (pinfunction "SPICS1_28") (pintype "passive"))
    )
    (net (code "74") (name "unconnected-(U16-CTS#-Pad9)") (class "Default")
      (node (ref "U16") (pin "9") (pinfunction "CTS#_9") (pintype "passive"))
    )
    (net (code "75") (name "unconnected-(U16-DCD#-Pad12)") (class "Default")
      (node (ref "U16") (pin "12") (pinfunction "DCD#_12") (pintype "passive"))
    )
    (net (code "76") (name "unconnected-(U16-DSR#-Pad10)") (class "Default")
      (node (ref "U16") (pin "10") (pinfunction "DSR#_10") (pintype "passive"))
    )
    (net (code "77") (name "unconnected-(U16-NC.-Pad7)") (class "Default")
      (node (ref "U16") (pin "7") (pinfunction "NC._7") (pintype "passive"))
    )
    (net (code "78") (name "unconnected-(U16-OUT#-Pad8)") (class "Default")
      (node (ref "U16") (pin "8") (pinfunction "OUT#_8") (pintype "passive"))
    )
    (net (code "79") (name "unconnected-(U16-R232-Pad15)") (class "Default")
      (node (ref "U16") (pin "15") (pinfunction "R232_15") (pintype "passive"))
    )
    (net (code "80") (name "unconnected-(U16-RI#-Pad11)") (class "Default")
      (node (ref "U16") (pin "11") (pinfunction "RI#_11") (pintype "passive"))
    )
    (net (code "81") (name "unconnected-(USB2-PadMH1)") (class "Default")
      (node (ref "USB2") (pin "MH1") (pinfunction "MH1_MH1") (pintype "passive"))
    )
    (net (code "82") (name "unconnected-(USB2-PadMH2)") (class "Default")
      (node (ref "USB2") (pin "MH2") (pinfunction "MH2_MH2") (pintype "passive"))
    )
    (net (code "83") (name "unconnected-(USB3-SBU1-PadA8)") (class "Default")
      (node (ref "USB3") (pin "A8") (pinfunction "SBU1_A8") (pintype "power_in+no_connect"))
    )
    (net (code "84") (name "unconnected-(USB3-SBU2-PadB8)") (class "Default")
      (node (ref "USB3") (pin "B8") (pinfunction "SBU2_B8") (pintype "power_in+no_connect"))
    )
  )
)
